# protoshield_mayfly_v1_a.net
KiCad netlist of a schematic drawn in EAGLE
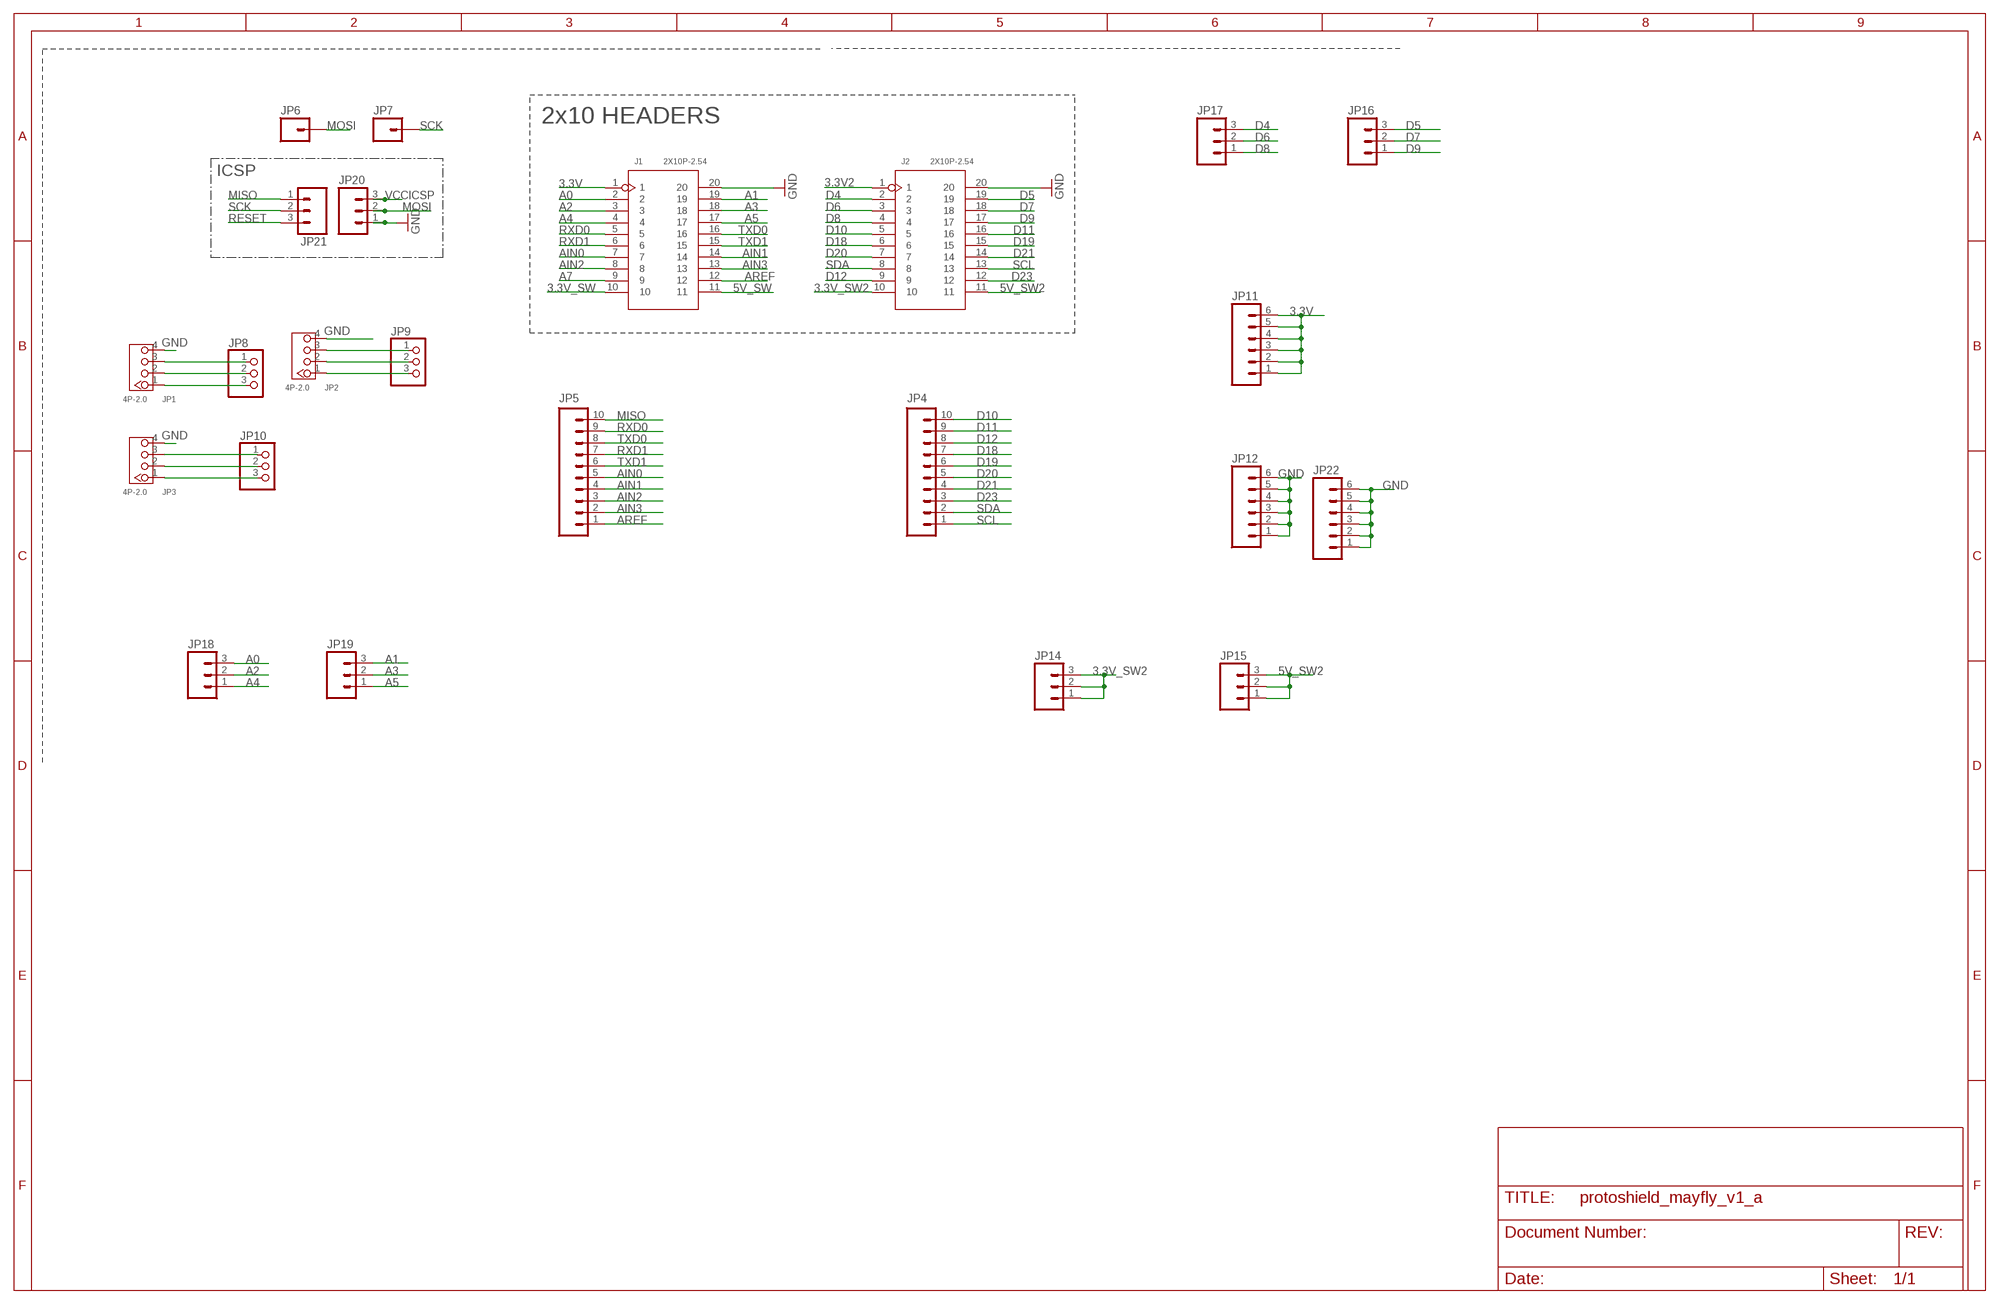
[diagram p0: schematic, sheet 1]

(export (version "E")
  (design (tool "Eeschema 10.0.6"))
  (components
    (comp (ref "J1")
      (value "2X10P-2.54")
      (footprint "eagle-import:H2X10-2.54")
      (fields (field (name "MPN") "F185-1210A0BA1"))
      (libsource (lib "eagle-import") (part "DIP-BLACK-FEMALE-HEADER(2X10P-2.54)-2.54"))
    )
    (comp (ref "J2")
      (value "2X10P-2.54")
      (footprint "eagle-import:H2X10-2.54")
      (fields (field (name "MPN") "F185-1210A0BA1"))
      (libsource (lib "eagle-import") (part "DIP-BLACK-FEMALE-HEADER(2X10P-2.54)-2.54"))
    )
    (comp (ref "JP1")
      (value "4P-2.0")
      (footprint "eagle-import:HW4-2.0")
      (libsource (lib "eagle-import") (part "GROVE-CONNECTOR-DIP(4P-2.0)"))
    )
    (comp (ref "JP2")
      (value "4P-2.0")
      (footprint "eagle-import:HW4-2.0")
      (libsource (lib "eagle-import") (part "GROVE-CONNECTOR-DIP(4P-2.0)"))
    )
    (comp (ref "JP3")
      (value "4P-2.0")
      (footprint "eagle-import:HW4-2.0")
      (libsource (lib "eagle-import") (part "GROVE-CONNECTOR-DIP(4P-2.0)"))
    )
    (comp (ref "JP4")
      (value "M10NO_SILK_PTH_FEMALE")
      (footprint "eagle-import:1X10_NO_SILK")
      (libsource (lib "eagle-import") (part "M10NO_SILK_PTH_FEMALE"))
    )
    (comp (ref "JP5")
      (value "M10NO_SILK_PTH_FEMALE")
      (footprint "eagle-import:1X10_NO_SILK")
      (libsource (lib "eagle-import") (part "M10NO_SILK_PTH_FEMALE"))
    )
    (comp (ref "JP6")
      (value "M01PTH_NO_SILK_YES_STOP")
      (footprint "eagle-import:1X01_NO_SILK")
      (libsource (lib "eagle-import") (part "M01PTH_NO_SILK_YES_STOP"))
    )
    (comp (ref "JP7")
      (value "M01PTH_NO_SILK_YES_STOP")
      (footprint "eagle-import:1X01_NO_SILK")
      (libsource (lib "eagle-import") (part "M01PTH_NO_SILK_YES_STOP"))
    )
    (comp (ref "JP8")
      (value "PINHD-1X3CB")
      (footprint "eagle-import:1X03-CLEANBIG")
      (libsource (lib "eagle-import") (part "PINHD-1X3CB"))
    )
    (comp (ref "JP9")
      (value "PINHD-1X3CB")
      (footprint "eagle-import:1X03-CLEANBIG")
      (libsource (lib "eagle-import") (part "PINHD-1X3CB"))
    )
    (comp (ref "JP10")
      (value "PINHD-1X3CB")
      (footprint "eagle-import:1X03-CLEANBIG")
      (libsource (lib "eagle-import") (part "PINHD-1X3CB"))
    )
    (comp (ref "JP11")
      (value "M06NO_SILK_FEMALE_PTH")
      (footprint "eagle-import:1X06_NO_SILK")
      (libsource (lib "eagle-import") (part "M06NO_SILK_FEMALE_PTH"))
    )
    (comp (ref "JP12")
      (value "M06NO_SILK_YES_STOP")
      (footprint "eagle-import:1X06_NO_SILK_YES_STOP")
      (libsource (lib "eagle-import") (part "M06NO_SILK_YES_STOP"))
    )
    (comp (ref "JP14")
      (value "M031X03_NO_SILK")
      (footprint "eagle-import:1X03_NO_SILK")
      (libsource (lib "eagle-import") (part "M031X03_NO_SILK"))
    )
    (comp (ref "JP15")
      (value "M031X03_NO_SILK")
      (footprint "eagle-import:1X03_NO_SILK")
      (libsource (lib "eagle-import") (part "M031X03_NO_SILK"))
    )
    (comp (ref "JP16")
      (value "M031X03_NO_SILK")
      (footprint "eagle-import:1X03_NO_SILK")
      (libsource (lib "eagle-import") (part "M031X03_NO_SILK"))
    )
    (comp (ref "JP17")
      (value "M031X03_NO_SILK")
      (footprint "eagle-import:1X03_NO_SILK")
      (libsource (lib "eagle-import") (part "M031X03_NO_SILK"))
    )
    (comp (ref "JP18")
      (value "M031X03_NO_SILK")
      (footprint "eagle-import:1X03_NO_SILK")
      (libsource (lib "eagle-import") (part "M031X03_NO_SILK"))
    )
    (comp (ref "JP19")
      (value "M031X03_NO_SILK")
      (footprint "eagle-import:1X03_NO_SILK")
      (libsource (lib "eagle-import") (part "M031X03_NO_SILK"))
    )
    (comp (ref "JP20")
      (value "M031X03_NO_SILK")
      (footprint "eagle-import:1X03_NO_SILK")
      (libsource (lib "eagle-import") (part "M031X03_NO_SILK"))
    )
    (comp (ref "JP21")
      (value "M031X03_NO_SILK")
      (footprint "eagle-import:1X03_NO_SILK")
      (libsource (lib "eagle-import") (part "M031X03_NO_SILK"))
    )
    (comp (ref "JP22")
      (value "M06NO_SILK_YES_STOP")
      (footprint "eagle-import:1X06_NO_SILK_YES_STOP")
      (libsource (lib "eagle-import") (part "M06NO_SILK_YES_STOP"))
    )
  )
  (nets
    (net (code "1") (name "/3.3V") (class "Default")
      (node (ref "J1") (pin "1") (pinfunction "1_1") (pintype "bidirectional"))
      (node (ref "JP11") (pin "1") (pinfunction "1_1") (pintype "passive"))
      (node (ref "JP11") (pin "2") (pinfunction "2_2") (pintype "passive"))
      (node (ref "JP11") (pin "3") (pinfunction "3_3") (pintype "passive"))
      (node (ref "JP11") (pin "4") (pinfunction "4_4") (pintype "passive"))
      (node (ref "JP11") (pin "5") (pinfunction "5_5") (pintype "passive"))
      (node (ref "JP11") (pin "6") (pinfunction "6_6") (pintype "passive"))
    )
    (net (code "2") (name "/3.3V2") (class "Default")
      (node (ref "J2") (pin "1") (pinfunction "1_1") (pintype "bidirectional"))
    )
    (net (code "3") (name "/3.3V_SW") (class "Default")
      (node (ref "J1") (pin "10") (pinfunction "10_10") (pintype "bidirectional"))
    )
    (net (code "4") (name "/3.3V_SW2") (class "Default")
      (node (ref "J2") (pin "10") (pinfunction "10_10") (pintype "bidirectional"))
      (node (ref "JP14") (pin "1") (pinfunction "1_1") (pintype "passive"))
      (node (ref "JP14") (pin "2") (pinfunction "2_2") (pintype "passive"))
      (node (ref "JP14") (pin "3") (pinfunction "3_3") (pintype "passive"))
    )
    (net (code "5") (name "/5V_SW") (class "Default")
      (node (ref "J1") (pin "11") (pinfunction "11_11") (pintype "bidirectional"))
    )
    (net (code "6") (name "/5V_SW2") (class "Default")
      (node (ref "J2") (pin "11") (pinfunction "11_11") (pintype "bidirectional"))
      (node (ref "JP15") (pin "1") (pinfunction "1_1") (pintype "passive"))
      (node (ref "JP15") (pin "2") (pinfunction "2_2") (pintype "passive"))
      (node (ref "JP15") (pin "3") (pinfunction "3_3") (pintype "passive"))
    )
    (net (code "7") (name "/A0") (class "Default")
      (node (ref "J1") (pin "2") (pinfunction "2_2") (pintype "bidirectional"))
      (node (ref "JP18") (pin "3") (pinfunction "3_3") (pintype "passive"))
    )
    (net (code "8") (name "/A1") (class "Default")
      (node (ref "J1") (pin "19") (pinfunction "19_19") (pintype "bidirectional"))
      (node (ref "JP19") (pin "3") (pinfunction "3_3") (pintype "passive"))
    )
    (net (code "9") (name "/A2") (class "Default")
      (node (ref "J1") (pin "3") (pinfunction "3_3") (pintype "bidirectional"))
      (node (ref "JP18") (pin "2") (pinfunction "2_2") (pintype "passive"))
    )
    (net (code "10") (name "/A3") (class "Default")
      (node (ref "J1") (pin "18") (pinfunction "18_18") (pintype "bidirectional"))
      (node (ref "JP19") (pin "2") (pinfunction "2_2") (pintype "passive"))
    )
    (net (code "11") (name "/A4") (class "Default")
      (node (ref "J1") (pin "4") (pinfunction "4_4") (pintype "bidirectional"))
      (node (ref "JP18") (pin "1") (pinfunction "1_1") (pintype "passive"))
    )
    (net (code "12") (name "/A5") (class "Default")
      (node (ref "J1") (pin "17") (pinfunction "17_17") (pintype "bidirectional"))
      (node (ref "JP19") (pin "1") (pinfunction "1_1") (pintype "passive"))
    )
    (net (code "13") (name "/A7") (class "Default")
      (node (ref "J1") (pin "9") (pinfunction "9_9") (pintype "bidirectional"))
    )
    (net (code "14") (name "/AIN0") (class "Default")
      (node (ref "J1") (pin "7") (pinfunction "7_7") (pintype "bidirectional"))
      (node (ref "JP5") (pin "5") (pinfunction "5_5") (pintype "passive"))
    )
    (net (code "15") (name "/AIN1") (class "Default")
      (node (ref "J1") (pin "14") (pinfunction "14_14") (pintype "bidirectional"))
      (node (ref "JP5") (pin "4") (pinfunction "4_4") (pintype "passive"))
    )
    (net (code "16") (name "/AIN2") (class "Default")
      (node (ref "J1") (pin "8") (pinfunction "8_8") (pintype "bidirectional"))
      (node (ref "JP5") (pin "3") (pinfunction "3_3") (pintype "passive"))
    )
    (net (code "17") (name "/AIN3") (class "Default")
      (node (ref "J1") (pin "13") (pinfunction "13_13") (pintype "bidirectional"))
      (node (ref "JP5") (pin "2") (pinfunction "2_2") (pintype "passive"))
    )
    (net (code "18") (name "/AREF") (class "Default")
      (node (ref "J1") (pin "12") (pinfunction "12_12") (pintype "bidirectional"))
      (node (ref "JP5") (pin "1") (pinfunction "1_1") (pintype "passive"))
    )
    (net (code "19") (name "/D4") (class "Default")
      (node (ref "J2") (pin "2") (pinfunction "2_2") (pintype "bidirectional"))
      (node (ref "JP17") (pin "3") (pinfunction "3_3") (pintype "passive"))
    )
    (net (code "20") (name "/D5") (class "Default")
      (node (ref "J2") (pin "19") (pinfunction "19_19") (pintype "bidirectional"))
      (node (ref "JP16") (pin "3") (pinfunction "3_3") (pintype "passive"))
    )
    (net (code "21") (name "/D6") (class "Default")
      (node (ref "J2") (pin "3") (pinfunction "3_3") (pintype "bidirectional"))
      (node (ref "JP17") (pin "2") (pinfunction "2_2") (pintype "passive"))
    )
    (net (code "22") (name "/D7") (class "Default")
      (node (ref "J2") (pin "18") (pinfunction "18_18") (pintype "bidirectional"))
      (node (ref "JP16") (pin "2") (pinfunction "2_2") (pintype "passive"))
    )
    (net (code "23") (name "/D8") (class "Default")
      (node (ref "J2") (pin "4") (pinfunction "4_4") (pintype "bidirectional"))
      (node (ref "JP17") (pin "1") (pinfunction "1_1") (pintype "passive"))
    )
    (net (code "24") (name "/D9") (class "Default")
      (node (ref "J2") (pin "17") (pinfunction "17_17") (pintype "bidirectional"))
      (node (ref "JP16") (pin "1") (pinfunction "1_1") (pintype "passive"))
    )
    (net (code "25") (name "/D10") (class "Default")
      (node (ref "J2") (pin "5") (pinfunction "5_5") (pintype "bidirectional"))
      (node (ref "JP4") (pin "10") (pinfunction "10_10") (pintype "passive"))
    )
    (net (code "26") (name "/D11") (class "Default")
      (node (ref "J2") (pin "16") (pinfunction "16_16") (pintype "bidirectional"))
      (node (ref "JP4") (pin "9") (pinfunction "9_9") (pintype "passive"))
    )
    (net (code "27") (name "/D12") (class "Default")
      (node (ref "J2") (pin "9") (pinfunction "9_9") (pintype "bidirectional"))
      (node (ref "JP4") (pin "8") (pinfunction "8_8") (pintype "passive"))
    )
    (net (code "28") (name "/D18") (class "Default")
      (node (ref "J2") (pin "6") (pinfunction "6_6") (pintype "bidirectional"))
      (node (ref "JP4") (pin "7") (pinfunction "7_7") (pintype "passive"))
    )
    (net (code "29") (name "/D19") (class "Default")
      (node (ref "J2") (pin "15") (pinfunction "15_15") (pintype "bidirectional"))
      (node (ref "JP4") (pin "6") (pinfunction "6_6") (pintype "passive"))
    )
    (net (code "30") (name "/D20") (class "Default")
      (node (ref "J2") (pin "7") (pinfunction "7_7") (pintype "bidirectional"))
      (node (ref "JP4") (pin "5") (pinfunction "5_5") (pintype "passive"))
    )
    (net (code "31") (name "/D21") (class "Default")
      (node (ref "J2") (pin "14") (pinfunction "14_14") (pintype "bidirectional"))
      (node (ref "JP4") (pin "4") (pinfunction "4_4") (pintype "passive"))
    )
    (net (code "32") (name "/D23") (class "Default")
      (node (ref "J2") (pin "12") (pinfunction "12_12") (pintype "bidirectional"))
      (node (ref "JP4") (pin "3") (pinfunction "3_3") (pintype "passive"))
    )
    (net (code "33") (name "/MISO") (class "Default")
      (node (ref "JP21") (pin "1") (pinfunction "1_1") (pintype "passive"))
      (node (ref "JP5") (pin "10") (pinfunction "10_10") (pintype "passive"))
    )
    (net (code "34") (name "/MOSI") (class "Default")
      (node (ref "JP20") (pin "2") (pinfunction "2_2") (pintype "passive"))
      (node (ref "JP6") (pin "1") (pinfunction "1_1") (pintype "passive"))
    )
    (net (code "35") (name "/RESET") (class "Default")
      (node (ref "JP21") (pin "3") (pinfunction "3_3") (pintype "passive"))
    )
    (net (code "36") (name "/RXD0") (class "Default")
      (node (ref "J1") (pin "5") (pinfunction "5_5") (pintype "bidirectional"))
      (node (ref "JP5") (pin "9") (pinfunction "9_9") (pintype "passive"))
    )
    (net (code "37") (name "/RXD1") (class "Default")
      (node (ref "J1") (pin "6") (pinfunction "6_6") (pintype "bidirectional"))
      (node (ref "JP5") (pin "7") (pinfunction "7_7") (pintype "passive"))
    )
    (net (code "38") (name "/SCK") (class "Default")
      (node (ref "JP21") (pin "2") (pinfunction "2_2") (pintype "passive"))
      (node (ref "JP7") (pin "1") (pinfunction "1_1") (pintype "passive"))
    )
    (net (code "39") (name "/SCL") (class "Default")
      (node (ref "J2") (pin "13") (pinfunction "13_13") (pintype "bidirectional"))
      (node (ref "JP4") (pin "1") (pinfunction "1_1") (pintype "passive"))
    )
    (net (code "40") (name "/SDA") (class "Default")
      (node (ref "J2") (pin "8") (pinfunction "8_8") (pintype "bidirectional"))
      (node (ref "JP4") (pin "2") (pinfunction "2_2") (pintype "passive"))
    )
    (net (code "41") (name "/TXD0") (class "Default")
      (node (ref "J1") (pin "16") (pinfunction "16_16") (pintype "bidirectional"))
      (node (ref "JP5") (pin "8") (pinfunction "8_8") (pintype "passive"))
    )
    (net (code "42") (name "/TXD1") (class "Default")
      (node (ref "J1") (pin "15") (pinfunction "15_15") (pintype "bidirectional"))
      (node (ref "JP5") (pin "6") (pinfunction "6_6") (pintype "passive"))
    )
    (net (code "43") (name "/VCCICSP") (class "Default")
      (node (ref "JP20") (pin "3") (pinfunction "3_3") (pintype "passive"))
    )
    (net (code "44") (name "GND") (class "Default")
      (node (ref "J1") (pin "20") (pinfunction "20_20") (pintype "bidirectional"))
      (node (ref "J2") (pin "20") (pinfunction "20_20") (pintype "bidirectional"))
      (node (ref "JP1") (pin "4") (pinfunction "4_4") (pintype "bidirectional"))
      (node (ref "JP12") (pin "1") (pinfunction "1_1") (pintype "passive"))
      (node (ref "JP12") (pin "2") (pinfunction "2_2") (pintype "passive"))
      (node (ref "JP12") (pin "3") (pinfunction "3_3") (pintype "passive"))
      (node (ref "JP12") (pin "4") (pinfunction "4_4") (pintype "passive"))
      (node (ref "JP12") (pin "5") (pinfunction "5_5") (pintype "passive"))
      (node (ref "JP12") (pin "6") (pinfunction "6_6") (pintype "passive"))
      (node (ref "JP2") (pin "4") (pinfunction "4_4") (pintype "bidirectional"))
      (node (ref "JP20") (pin "1") (pinfunction "1_1") (pintype "passive"))
      (node (ref "JP22") (pin "1") (pinfunction "1_1") (pintype "passive"))
      (node (ref "JP22") (pin "2") (pinfunction "2_2") (pintype "passive"))
      (node (ref "JP22") (pin "3") (pinfunction "3_3") (pintype "passive"))
      (node (ref "JP22") (pin "4") (pinfunction "4_4") (pintype "passive"))
      (node (ref "JP22") (pin "5") (pinfunction "5_5") (pintype "passive"))
      (node (ref "JP22") (pin "6") (pinfunction "6_6") (pintype "passive"))
      (node (ref "JP3") (pin "4") (pinfunction "4_4") (pintype "bidirectional"))
    )
    (net (code "45") (name "Net-(JP1-Pad1)") (class "Default")
      (node (ref "JP1") (pin "1") (pinfunction "1_1") (pintype "bidirectional"))
      (node (ref "JP8") (pin "3") (pinfunction "3_3") (pintype "passive"))
    )
    (net (code "46") (name "Net-(JP1-Pad2)") (class "Default")
      (node (ref "JP1") (pin "2") (pinfunction "2_2") (pintype "bidirectional"))
      (node (ref "JP8") (pin "2") (pinfunction "2_2") (pintype "passive"))
    )
    (net (code "47") (name "Net-(JP1-Pad3)") (class "Default")
      (node (ref "JP1") (pin "3") (pinfunction "3_3") (pintype "bidirectional"))
      (node (ref "JP8") (pin "1") (pinfunction "1_1") (pintype "passive"))
    )
    (net (code "48") (name "Net-(JP2-Pad1)") (class "Default")
      (node (ref "JP2") (pin "1") (pinfunction "1_1") (pintype "bidirectional"))
      (node (ref "JP9") (pin "3") (pinfunction "3_3") (pintype "passive"))
    )
    (net (code "49") (name "Net-(JP2-Pad2)") (class "Default")
      (node (ref "JP2") (pin "2") (pinfunction "2_2") (pintype "bidirectional"))
      (node (ref "JP9") (pin "2") (pinfunction "2_2") (pintype "passive"))
    )
    (net (code "50") (name "Net-(JP2-Pad3)") (class "Default")
      (node (ref "JP2") (pin "3") (pinfunction "3_3") (pintype "bidirectional"))
      (node (ref "JP9") (pin "1") (pinfunction "1_1") (pintype "passive"))
    )
    (net (code "51") (name "Net-(JP10-Pad1)") (class "Default")
      (node (ref "JP10") (pin "1") (pinfunction "1_1") (pintype "passive"))
      (node (ref "JP3") (pin "3") (pinfunction "3_3") (pintype "bidirectional"))
    )
    (net (code "52") (name "Net-(JP10-Pad2)") (class "Default")
      (node (ref "JP10") (pin "2") (pinfunction "2_2") (pintype "passive"))
      (node (ref "JP3") (pin "2") (pinfunction "2_2") (pintype "bidirectional"))
    )
    (net (code "53") (name "Net-(JP10-Pad3)") (class "Default")
      (node (ref "JP10") (pin "3") (pinfunction "3_3") (pintype "passive"))
      (node (ref "JP3") (pin "1") (pinfunction "1_1") (pintype "bidirectional"))
    )
  )
)
